# StepDirDriver.net
KiCad netlist of a schematic drawn in Altium Designer
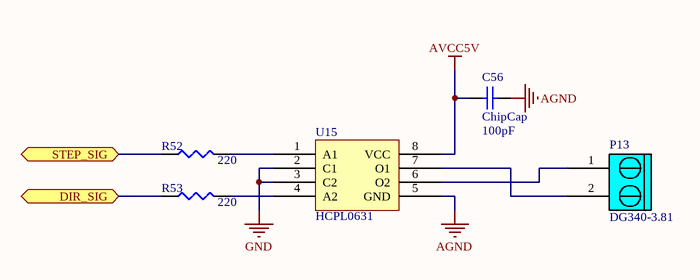
[diagram p0: StepDirDriver.SchDoc]

(export (version "E")
  (design (tool "Eeschema 10.0.6"))
  (components
    (comp (ref "C56")
      (value "ChipCap")
      (footprint "CAP0805")
      (description "Capacitor")
      (fields (field (name "ALTIUM_VALUE") "100pF") (field (name "PUBLISHER") "Altium Limited"))
      (libsource (lib "Common Devices") (part "ChipCap"))
    )
    (comp (ref "P13")
      (value "DG340-3.81")
      (footprint "DG340-3.81-02P-00A(H)")
      (description "Terminal block")
      (libsource (lib "Connectors") (part "DG340-3.81-02P"))
    )
    (comp (ref "R52")
      (value "220")
      (footprint "RES0805")
      (description "Chip resistor")
      (fields (field (name "Comment") "ChipRes"))
      (libsource (lib "Common Devices") (part "ChipRes"))
    )
    (comp (ref "R53")
      (value "220")
      (footprint "RES0805")
      (description "Chip resistor")
      (fields (field (name "Comment") "ChipRes"))
      (libsource (lib "Common Devices") (part "ChipRes"))
    )
    (comp (ref "U15")
      (value "HCPL0631")
      (footprint "SOIC8")
      (description "2-channel opto-coupler")
      (libsource (lib "Avago Optocouplers") (part "HCPL0631"))
    )
  )
  (nets
    (net (code "1") (name "/DIR_SIG") (class "Default") (node (ref "R53") (pin "1") (pintype "passive")))
    (net (code "2") (name "/STEP_SIG") (class "Default") (node (ref "R52") (pin "1") (pintype "passive")))
    (net (code "3") (name "AGND") (class "Default")
      (node (ref "C56") (pin "2") (pinfunction "2_2") (pintype "passive"))
      (node (ref "U15") (pin "5") (pinfunction "GND_5") (pintype "passive"))
    )
    (net (code "4") (name "AVCC5V") (class "Default")
      (node (ref "C56") (pin "1") (pinfunction "1_1") (pintype "passive"))
      (node (ref "U15") (pin "8") (pinfunction "VCC_8") (pintype "passive"))
    )
    (net (code "5") (name "GND") (class "Default")
      (node (ref "U15") (pin "2") (pinfunction "C1_2") (pintype "passive"))
      (node (ref "U15") (pin "3") (pinfunction "C2_3") (pintype "passive"))
    )
    (net (code "6") (name "Net-(U15-A1)") (class "Default")
      (node (ref "R52") (pin "2") (pintype "passive"))
      (node (ref "U15") (pin "1") (pinfunction "A1_1") (pintype "passive"))
    )
    (net (code "7") (name "Net-(U15-A2)") (class "Default")
      (node (ref "R53") (pin "2") (pintype "passive"))
      (node (ref "U15") (pin "4") (pinfunction "A2_4") (pintype "passive"))
    )
    (net (code "8") (name "Net-(U15-O1)") (class "Default")
      (node (ref "P13") (pin "2") (pinfunction "2_2") (pintype "passive"))
      (node (ref "U15") (pin "7") (pinfunction "O1_7") (pintype "passive"))
    )
    (net (code "9") (name "Net-(U15-O2)") (class "Default")
      (node (ref "P13") (pin "1") (pinfunction "1_1") (pintype "passive"))
      (node (ref "U15") (pin "6") (pinfunction "O2_6") (pintype "passive"))
    )
  )
)
